# just_a_switch-mk-2_2.net
KiCad netlist of a schematic drawn in EAGLE
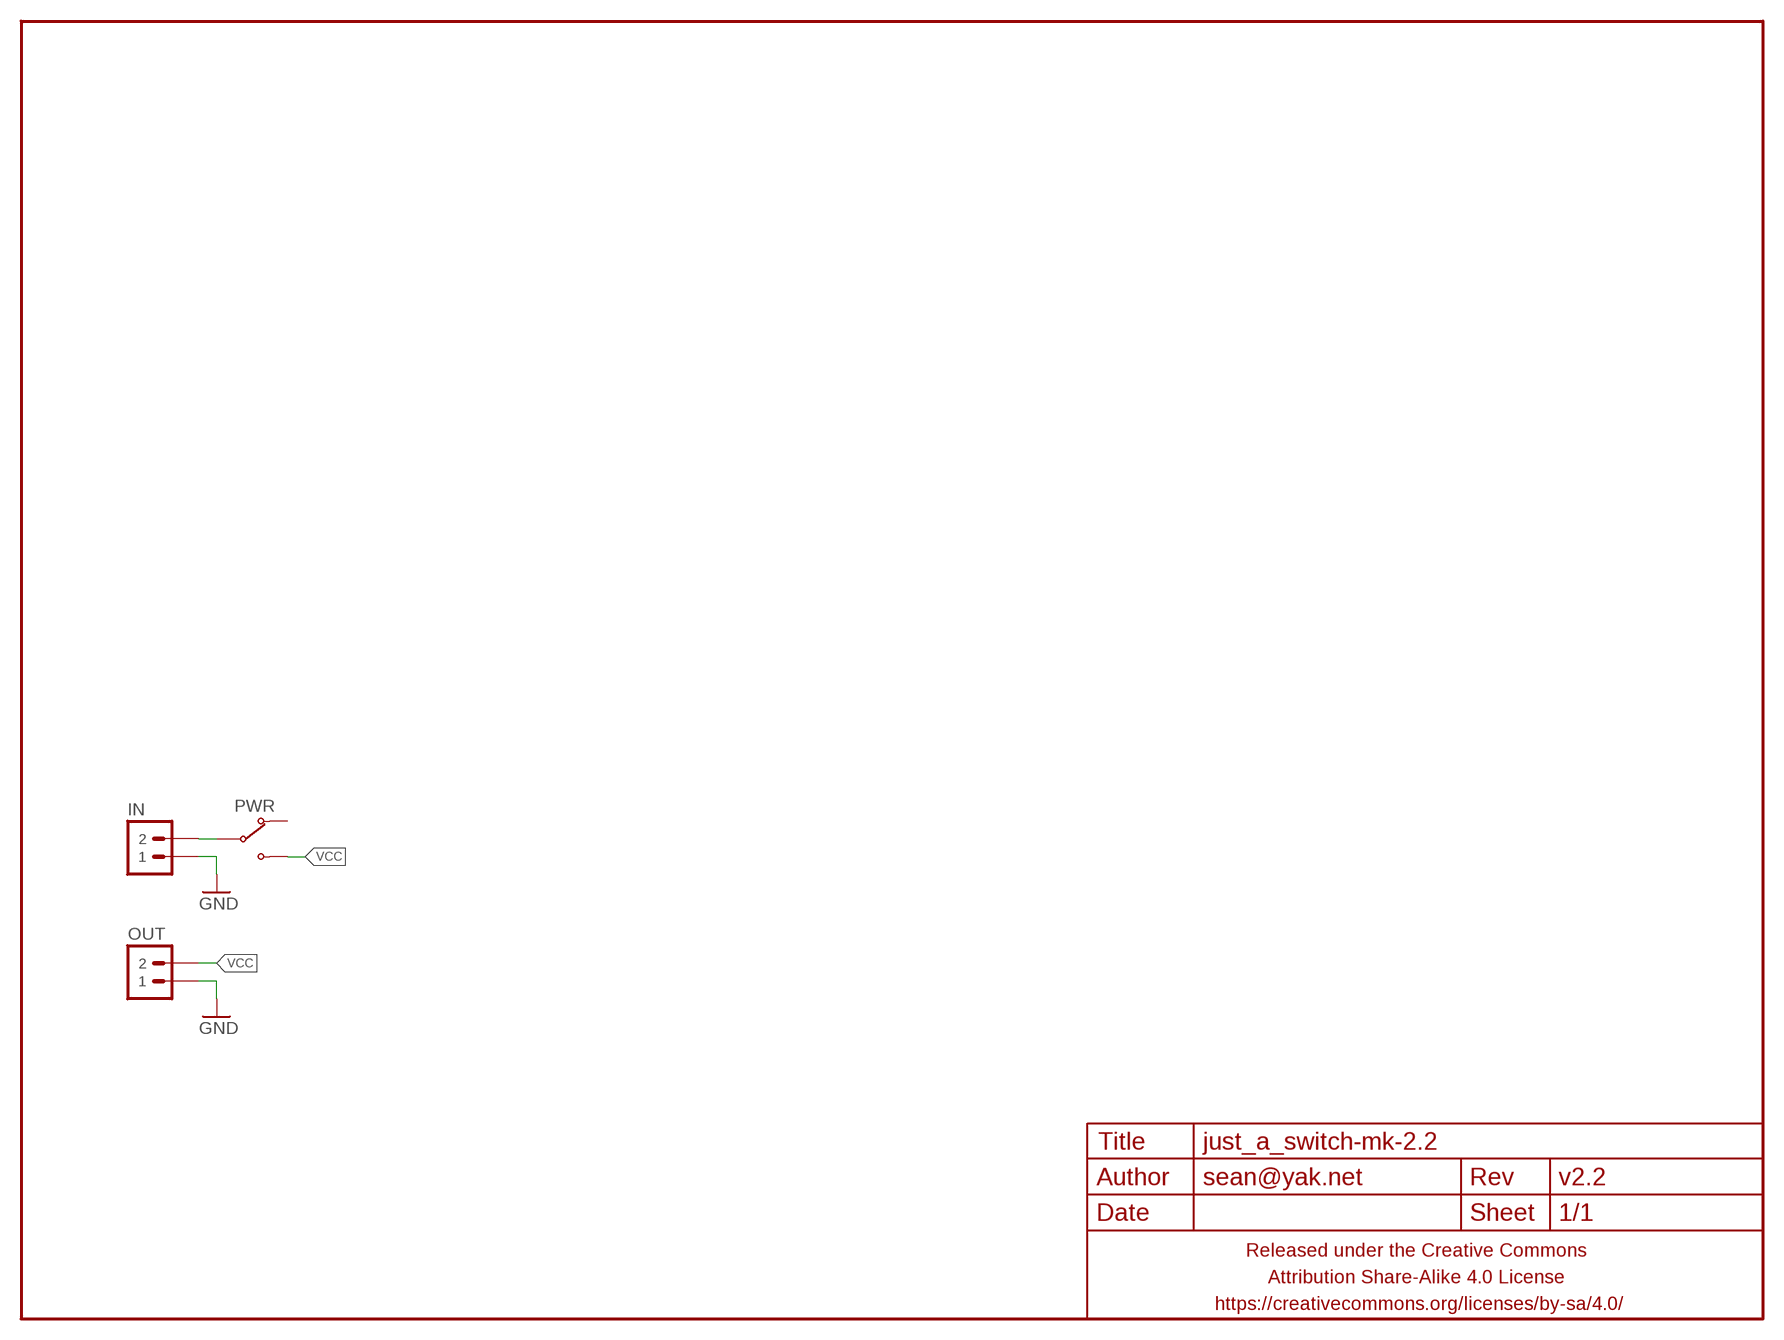
[diagram p0: schematic, sheet 1]

(export (version "E")
  (design (tool "Eeschema 10.0.6"))
  (components
    (comp (ref "FRAME1")
      (value "FRAME-LETTERNO_PACKAGE")
      (footprint "eagle-import:DUMMY")
      (fields (field (name "DESIGNER") "sean@yak.net") (field (name "VERSION") "v2.2"))
      (libsource (lib "eagle-import") (part "FRAME-LETTERNO_PACKAGE"))
    )
    (comp (ref "IN")
      (value "M02JST-PH-VERT-R+")
      (footprint "eagle-import:JST-2-PH-VERT-PTH-R+")
      (libsource (lib "eagle-import") (part "M02JST-PH-VERT-R+"))
    )
    (comp (ref "OUT")
      (value "M02JST-PH-VERT-R+")
      (footprint "eagle-import:JST-2-PH-VERT-PTH-R+")
      (libsource (lib "eagle-import") (part "M02JST-PH-VERT-R+"))
    )
    (comp (ref "PWR")
      (value "SWITCH-SPDTPTH-RA-2.54MM")
      (footprint "eagle-import:SPDT-RA-2.54MM")
      (libsource (lib "eagle-import") (part "SWITCH-SPDTPTH-RA-2.54MM"))
    )
  )
  (nets
    (net (code "1") (name "GND") (class "Default")
      (node (ref "IN") (pin "1") (pinfunction "1_1") (pintype "passive"))
      (node (ref "OUT") (pin "1") (pinfunction "1_1") (pintype "passive"))
    )
    (net (code "2") (name "Net-(PWR-COM)") (class "Default")
      (node (ref "IN") (pin "2") (pinfunction "2_2") (pintype "passive"))
      (node (ref "PWR") (pin "2") (pinfunction "COM_2") (pintype "passive"))
    )
    (net (code "3") (name "VCC") (class "Default")
      (node (ref "OUT") (pin "2") (pinfunction "2_2") (pintype "passive"))
      (node (ref "PWR") (pin "3") (pinfunction "NO_3") (pintype "passive"))
    )
    (net (code "4") (name "unconnected-(PWR-NC-Pad1)") (class "Default")
      (node (ref "PWR") (pin "1") (pinfunction "NC_1") (pintype "passive"))
    )
  )
)
